# lixie_digit_mini.net
KiCad netlist of a schematic drawn in EAGLE
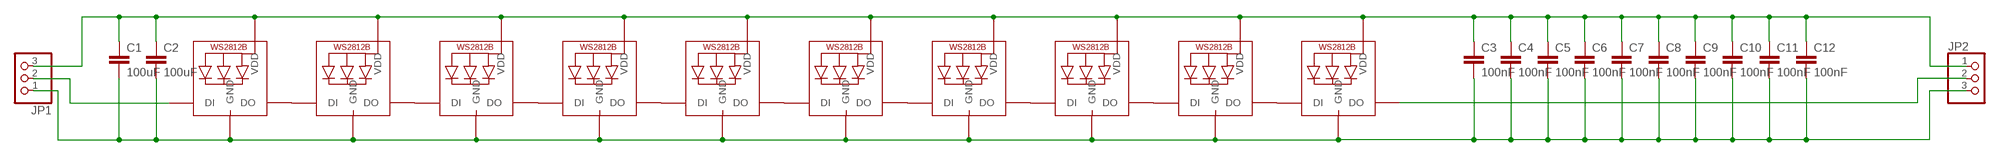
[diagram p0: schematic, sheet 1]

(export (version "E")
  (design (tool "Eeschema 10.0.6"))
  (components
    (comp (ref "C1")
      (value "100uF")
      (footprint "eagle-import:C1206K")
      (libsource (lib "eagle-import") (part "C-EUC1206K"))
    )
    (comp (ref "C2")
      (value "100uF")
      (footprint "eagle-import:C1206K")
      (libsource (lib "eagle-import") (part "C-EUC1206K"))
    )
    (comp (ref "C3")
      (value "100nF")
      (footprint "eagle-import:C0805K")
      (libsource (lib "eagle-import") (part "C-EUC0805K"))
    )
    (comp (ref "C4")
      (value "100nF")
      (footprint "eagle-import:C0805K")
      (libsource (lib "eagle-import") (part "C-EUC0805K"))
    )
    (comp (ref "C5")
      (value "100nF")
      (footprint "eagle-import:C0805K")
      (libsource (lib "eagle-import") (part "C-EUC0805K"))
    )
    (comp (ref "C6")
      (value "100nF")
      (footprint "eagle-import:C0805K")
      (libsource (lib "eagle-import") (part "C-EUC0805K"))
    )
    (comp (ref "C7")
      (value "100nF")
      (footprint "eagle-import:C0805K")
      (libsource (lib "eagle-import") (part "C-EUC0805K"))
    )
    (comp (ref "C8")
      (value "100nF")
      (footprint "eagle-import:C0805K")
      (libsource (lib "eagle-import") (part "C-EUC0805K"))
    )
    (comp (ref "C9")
      (value "100nF")
      (footprint "eagle-import:C0805K")
      (libsource (lib "eagle-import") (part "C-EUC0805K"))
    )
    (comp (ref "C10")
      (value "100nF")
      (footprint "eagle-import:C0805K")
      (libsource (lib "eagle-import") (part "C-EUC0805K"))
    )
    (comp (ref "C11")
      (value "100nF")
      (footprint "eagle-import:C0805K")
      (libsource (lib "eagle-import") (part "C-EUC0805K"))
    )
    (comp (ref "C12")
      (value "100nF")
      (footprint "eagle-import:C0805K")
      (libsource (lib "eagle-import") (part "C-EUC0805K"))
    )
    (comp (ref "JP1")
      (value "PINHD-1X3")
      (footprint "eagle-import:1X03")
      (libsource (lib "eagle-import") (part "PINHD-1X3"))
    )
    (comp (ref "JP2")
      (value "PINHD-1X3")
      (footprint "eagle-import:1X03")
      (libsource (lib "eagle-import") (part "PINHD-1X3"))
    )
    (comp (ref "LED1")
      (value "WS2812B5050")
      (footprint "eagle-import:WS2812B")
      (libsource (lib "eagle-import") (part "WS2812B5050"))
    )
    (comp (ref "LED2")
      (value "WS2812B5050")
      (footprint "eagle-import:WS2812B")
      (libsource (lib "eagle-import") (part "WS2812B5050"))
    )
    (comp (ref "LED3")
      (value "WS2812B5050")
      (footprint "eagle-import:WS2812B")
      (libsource (lib "eagle-import") (part "WS2812B5050"))
    )
    (comp (ref "LED4")
      (value "WS2812B5050")
      (footprint "eagle-import:WS2812B")
      (libsource (lib "eagle-import") (part "WS2812B5050"))
    )
    (comp (ref "LED5")
      (value "WS2812B5050")
      (footprint "eagle-import:WS2812B")
      (libsource (lib "eagle-import") (part "WS2812B5050"))
    )
    (comp (ref "LED6")
      (value "WS2812B5050")
      (footprint "eagle-import:WS2812B")
      (libsource (lib "eagle-import") (part "WS2812B5050"))
    )
    (comp (ref "LED7")
      (value "WS2812B5050")
      (footprint "eagle-import:WS2812B")
      (libsource (lib "eagle-import") (part "WS2812B5050"))
    )
    (comp (ref "LED8")
      (value "WS2812B5050")
      (footprint "eagle-import:WS2812B")
      (libsource (lib "eagle-import") (part "WS2812B5050"))
    )
    (comp (ref "LED9")
      (value "WS2812B5050")
      (footprint "eagle-import:WS2812B")
      (libsource (lib "eagle-import") (part "WS2812B5050"))
    )
    (comp (ref "LED10")
      (value "WS2812B5050")
      (footprint "eagle-import:WS2812B")
      (libsource (lib "eagle-import") (part "WS2812B5050"))
    )
  )
  (nets
    (net (code "1") (name "Net-(LED1-DI)") (class "Default")
      (node (ref "JP1") (pin "2") (pinfunction "2_2") (pintype "passive"))
      (node (ref "LED1") (pin "4-DIN") (pinfunction "DI_4-DIN") (pintype "input"))
    )
    (net (code "2") (name "Net-(LED1-DO)") (class "Default")
      (node (ref "LED1") (pin "2-DOUT") (pinfunction "DO_2-DOUT") (pintype "output"))
      (node (ref "LED2") (pin "4-DIN") (pinfunction "DI_4-DIN") (pintype "input"))
    )
    (net (code "3") (name "Net-(LED1-GND)") (class "Default")
      (node (ref "C1") (pin "2") (pinfunction "2_2") (pintype "passive"))
      (node (ref "C10") (pin "2") (pinfunction "2_2") (pintype "passive"))
      (node (ref "C11") (pin "2") (pinfunction "2_2") (pintype "passive"))
      (node (ref "C12") (pin "2") (pinfunction "2_2") (pintype "passive"))
      (node (ref "C2") (pin "2") (pinfunction "2_2") (pintype "passive"))
      (node (ref "C3") (pin "2") (pinfunction "2_2") (pintype "passive"))
      (node (ref "C4") (pin "2") (pinfunction "2_2") (pintype "passive"))
      (node (ref "C5") (pin "2") (pinfunction "2_2") (pintype "passive"))
      (node (ref "C6") (pin "2") (pinfunction "2_2") (pintype "passive"))
      (node (ref "C7") (pin "2") (pinfunction "2_2") (pintype "passive"))
      (node (ref "C8") (pin "2") (pinfunction "2_2") (pintype "passive"))
      (node (ref "C9") (pin "2") (pinfunction "2_2") (pintype "passive"))
      (node (ref "JP1") (pin "1") (pinfunction "1_1") (pintype "passive"))
      (node (ref "JP2") (pin "3") (pinfunction "3_3") (pintype "passive"))
      (node (ref "LED1") (pin "3-GND") (pinfunction "GND_3-GND") (pintype "power_in"))
      (node (ref "LED10") (pin "3-GND") (pinfunction "GND_3-GND") (pintype "power_in"))
      (node (ref "LED2") (pin "3-GND") (pinfunction "GND_3-GND") (pintype "power_in"))
      (node (ref "LED3") (pin "3-GND") (pinfunction "GND_3-GND") (pintype "power_in"))
      (node (ref "LED4") (pin "3-GND") (pinfunction "GND_3-GND") (pintype "power_in"))
      (node (ref "LED5") (pin "3-GND") (pinfunction "GND_3-GND") (pintype "power_in"))
      (node (ref "LED6") (pin "3-GND") (pinfunction "GND_3-GND") (pintype "power_in"))
      (node (ref "LED7") (pin "3-GND") (pinfunction "GND_3-GND") (pintype "power_in"))
      (node (ref "LED8") (pin "3-GND") (pinfunction "GND_3-GND") (pintype "power_in"))
      (node (ref "LED9") (pin "3-GND") (pinfunction "GND_3-GND") (pintype "power_in"))
    )
    (net (code "4") (name "Net-(LED1-VDD)") (class "Default")
      (node (ref "C1") (pin "1") (pinfunction "1_1") (pintype "passive"))
      (node (ref "C10") (pin "1") (pinfunction "1_1") (pintype "passive"))
      (node (ref "C11") (pin "1") (pinfunction "1_1") (pintype "passive"))
      (node (ref "C12") (pin "1") (pinfunction "1_1") (pintype "passive"))
      (node (ref "C2") (pin "1") (pinfunction "1_1") (pintype "passive"))
      (node (ref "C3") (pin "1") (pinfunction "1_1") (pintype "passive"))
      (node (ref "C4") (pin "1") (pinfunction "1_1") (pintype "passive"))
      (node (ref "C5") (pin "1") (pinfunction "1_1") (pintype "passive"))
      (node (ref "C6") (pin "1") (pinfunction "1_1") (pintype "passive"))
      (node (ref "C7") (pin "1") (pinfunction "1_1") (pintype "passive"))
      (node (ref "C8") (pin "1") (pinfunction "1_1") (pintype "passive"))
      (node (ref "C9") (pin "1") (pinfunction "1_1") (pintype "passive"))
      (node (ref "JP1") (pin "3") (pinfunction "3_3") (pintype "passive"))
      (node (ref "JP2") (pin "1") (pinfunction "1_1") (pintype "passive"))
      (node (ref "LED1") (pin "1-VDD") (pinfunction "VDD_1-VDD") (pintype "power_in"))
      (node (ref "LED10") (pin "1-VDD") (pinfunction "VDD_1-VDD") (pintype "power_in"))
      (node (ref "LED2") (pin "1-VDD") (pinfunction "VDD_1-VDD") (pintype "power_in"))
      (node (ref "LED3") (pin "1-VDD") (pinfunction "VDD_1-VDD") (pintype "power_in"))
      (node (ref "LED4") (pin "1-VDD") (pinfunction "VDD_1-VDD") (pintype "power_in"))
      (node (ref "LED5") (pin "1-VDD") (pinfunction "VDD_1-VDD") (pintype "power_in"))
      (node (ref "LED6") (pin "1-VDD") (pinfunction "VDD_1-VDD") (pintype "power_in"))
      (node (ref "LED7") (pin "1-VDD") (pinfunction "VDD_1-VDD") (pintype "power_in"))
      (node (ref "LED8") (pin "1-VDD") (pinfunction "VDD_1-VDD") (pintype "power_in"))
      (node (ref "LED9") (pin "1-VDD") (pinfunction "VDD_1-VDD") (pintype "power_in"))
    )
    (net (code "5") (name "Net-(LED2-DO)") (class "Default")
      (node (ref "LED2") (pin "2-DOUT") (pinfunction "DO_2-DOUT") (pintype "output"))
      (node (ref "LED3") (pin "4-DIN") (pinfunction "DI_4-DIN") (pintype "input"))
    )
    (net (code "6") (name "Net-(LED3-DO)") (class "Default")
      (node (ref "LED3") (pin "2-DOUT") (pinfunction "DO_2-DOUT") (pintype "output"))
      (node (ref "LED4") (pin "4-DIN") (pinfunction "DI_4-DIN") (pintype "input"))
    )
    (net (code "7") (name "Net-(LED4-DO)") (class "Default")
      (node (ref "LED4") (pin "2-DOUT") (pinfunction "DO_2-DOUT") (pintype "output"))
      (node (ref "LED5") (pin "4-DIN") (pinfunction "DI_4-DIN") (pintype "input"))
    )
    (net (code "8") (name "Net-(LED5-DO)") (class "Default")
      (node (ref "LED5") (pin "2-DOUT") (pinfunction "DO_2-DOUT") (pintype "output"))
      (node (ref "LED6") (pin "4-DIN") (pinfunction "DI_4-DIN") (pintype "input"))
    )
    (net (code "9") (name "Net-(LED6-DO)") (class "Default")
      (node (ref "LED6") (pin "2-DOUT") (pinfunction "DO_2-DOUT") (pintype "output"))
      (node (ref "LED7") (pin "4-DIN") (pinfunction "DI_4-DIN") (pintype "input"))
    )
    (net (code "10") (name "Net-(LED7-DO)") (class "Default")
      (node (ref "LED7") (pin "2-DOUT") (pinfunction "DO_2-DOUT") (pintype "output"))
      (node (ref "LED8") (pin "4-DIN") (pinfunction "DI_4-DIN") (pintype "input"))
    )
    (net (code "11") (name "Net-(LED8-DO)") (class "Default")
      (node (ref "LED8") (pin "2-DOUT") (pinfunction "DO_2-DOUT") (pintype "output"))
      (node (ref "LED9") (pin "4-DIN") (pinfunction "DI_4-DIN") (pintype "input"))
    )
    (net (code "12") (name "Net-(LED10-DI)") (class "Default")
      (node (ref "LED10") (pin "4-DIN") (pinfunction "DI_4-DIN") (pintype "input"))
      (node (ref "LED9") (pin "2-DOUT") (pinfunction "DO_2-DOUT") (pintype "output"))
    )
    (net (code "13") (name "Net-(LED10-DO)") (class "Default")
      (node (ref "JP2") (pin "2") (pinfunction "2_2") (pintype "passive"))
      (node (ref "LED10") (pin "2-DOUT") (pinfunction "DO_2-DOUT") (pintype "output"))
    )
  )
)
